# Connectors.net
KiCad netlist of a schematic drawn in Altium Designer
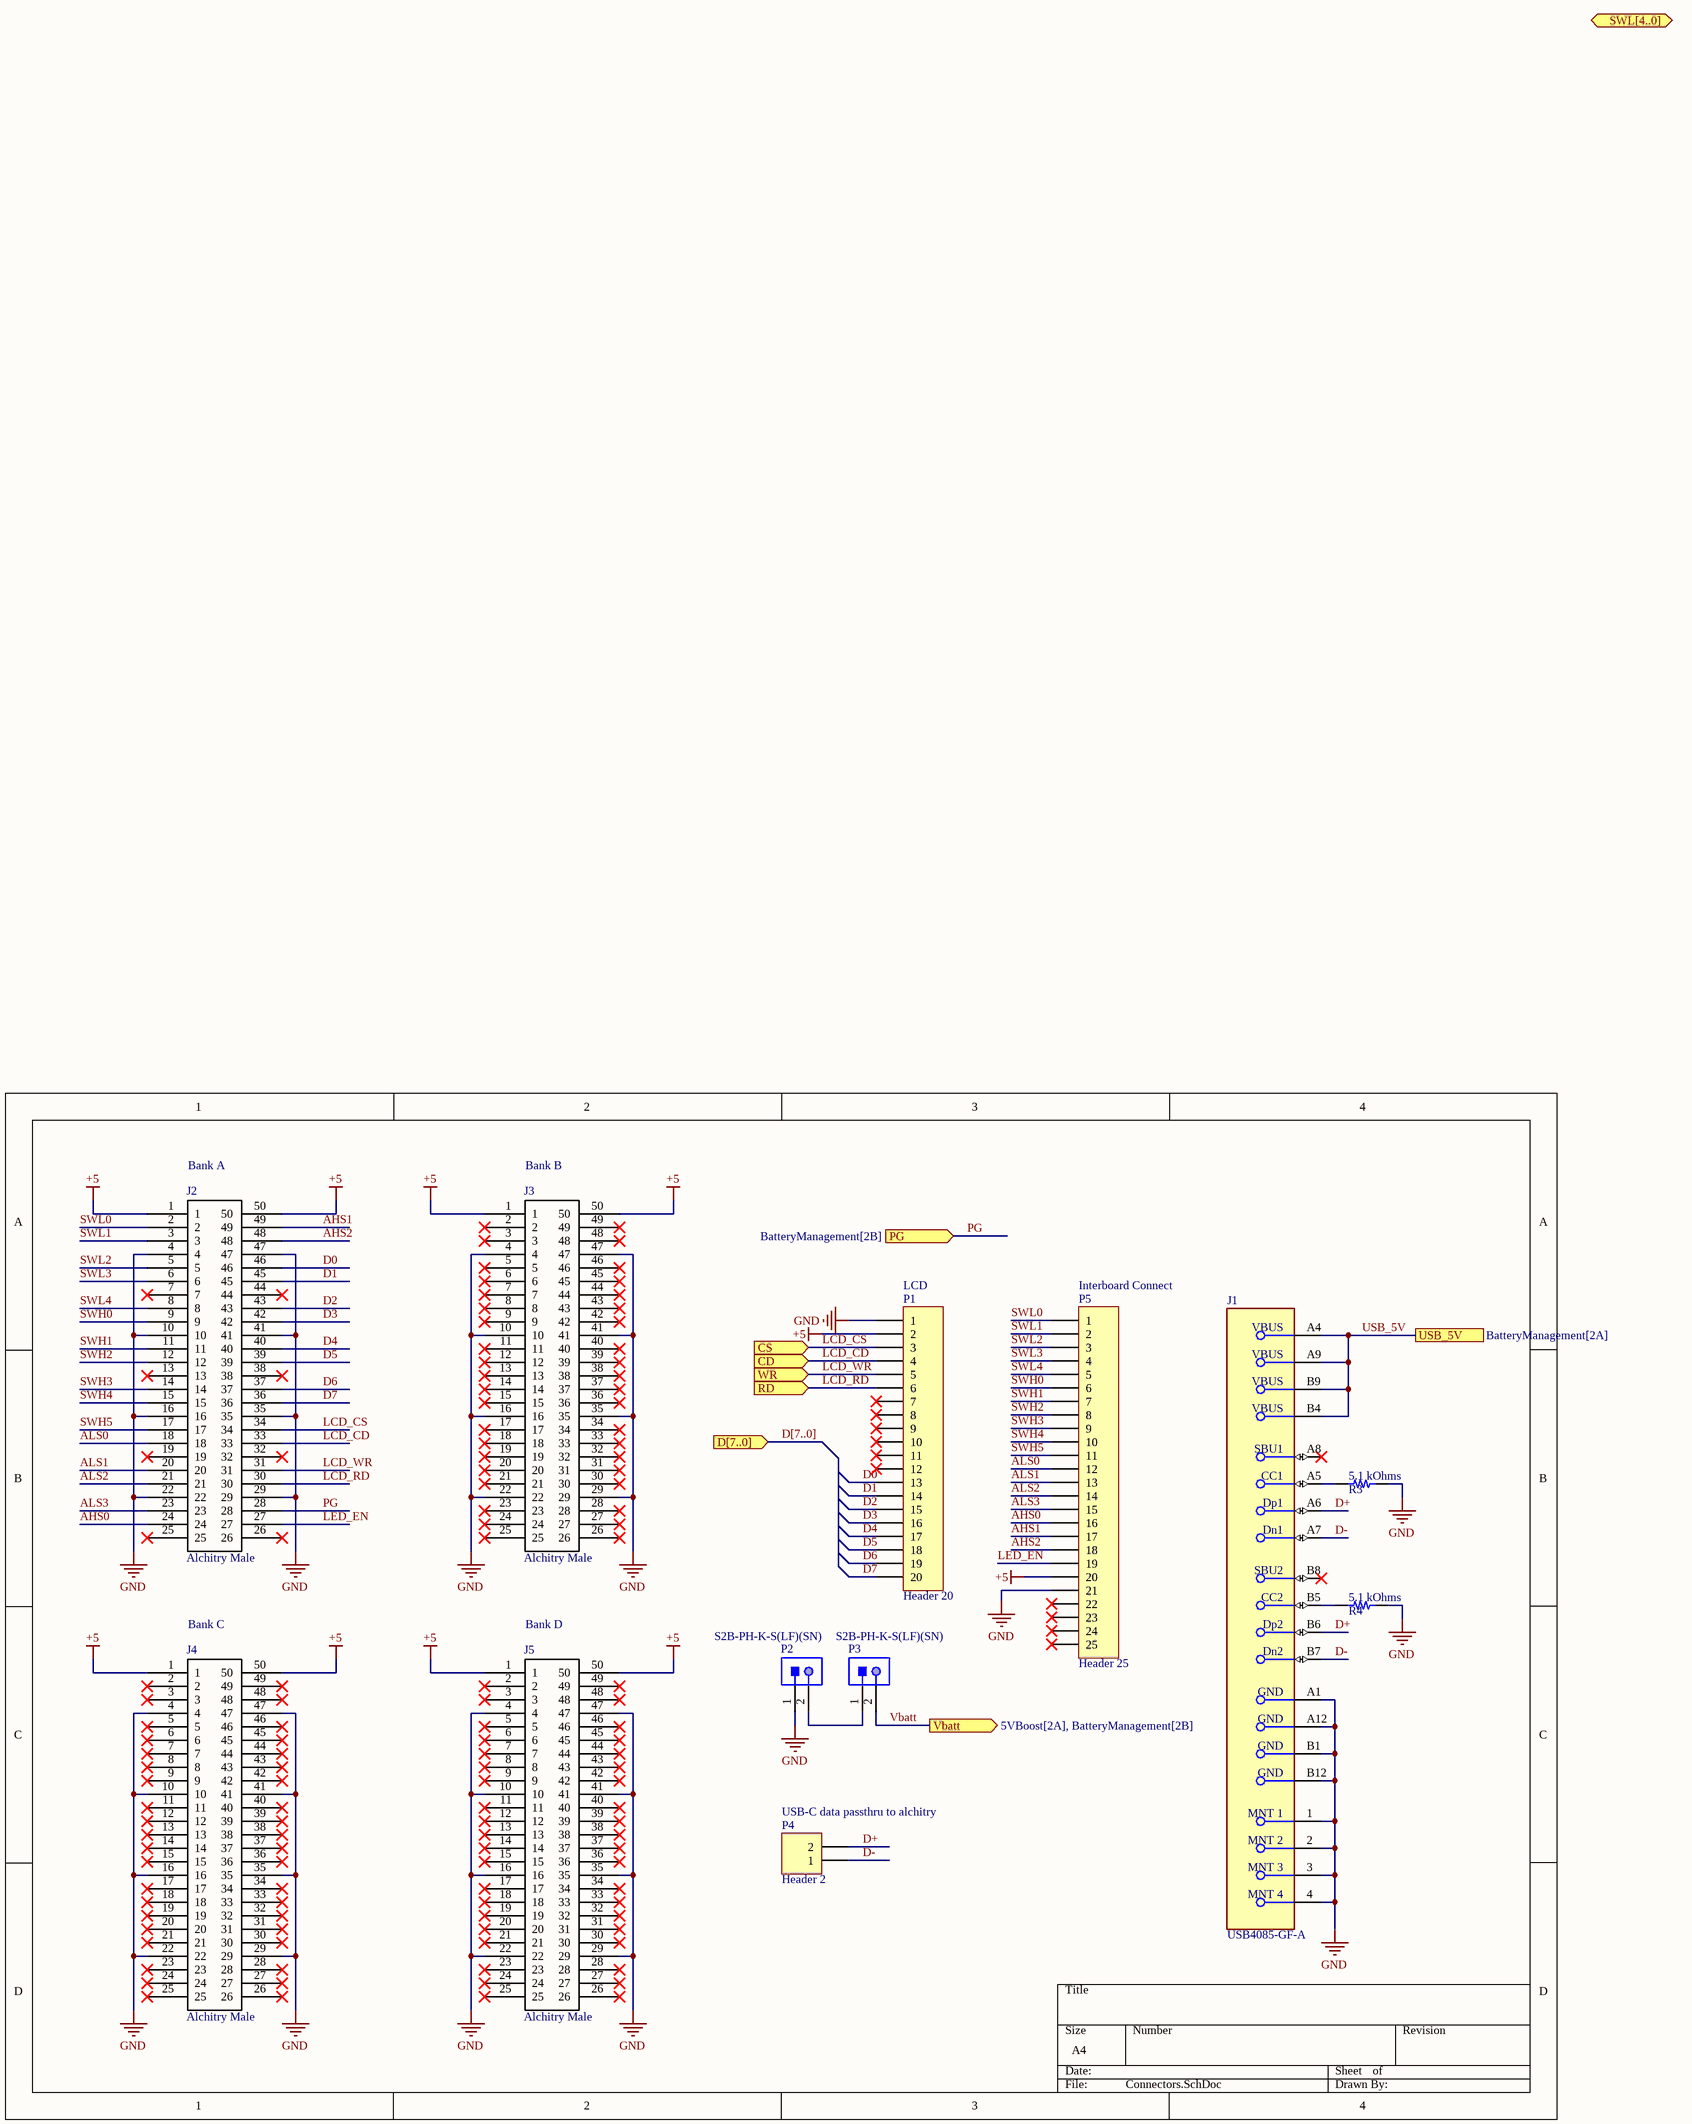
[diagram p0: Connectors.SchDoc]

(export (version "E")
  (design (tool "Eeschema 10.0.6"))
  (components
    (comp (ref "J1")
      (value "USB4085-GF-A")
      (footprint "FP-USB4085-GF-A-MFG")
      (description "CONN RCPT USB2.0 TYPE C 24POS RA")
      (libsource (lib "Altium Content Vault") (part "10fa745527c8b974685cbca3c197132"))
    )
    (comp (ref "J2")
      (value "Alchitry Male")
      (footprint "AlchitryMale")
      (libsource (lib "2020-09-26_17-27-19") (part "Alchitry Male"))
    )
    (comp (ref "J3")
      (value "Alchitry Male")
      (footprint "AlchitryMale")
      (libsource (lib "2020-09-26_17-27-19") (part "Alchitry Male"))
    )
    (comp (ref "J4")
      (value "Alchitry Male")
      (footprint "AlchitryMale")
      (libsource (lib "2020-09-26_17-27-19") (part "Alchitry Male"))
    )
    (comp (ref "J5")
      (value "Alchitry Male")
      (footprint "AlchitryMale")
      (libsource (lib "2020-09-26_17-27-19") (part "Alchitry Male"))
    )
    (comp (ref "P1")
      (value "Header 20")
      (footprint "HDR1X20")
      (description "Header, 20-Pin")
      (fields (field (name "PUBLISHER") "Altium Limited"))
      (libsource (lib "Miscellaneous Connectors") (part "Header 20"))
    )
    (comp (ref "P2")
      (value "S2B-PH-K-S(LF)(SN)")
      (footprint "JST-S2B-PH-K-S_V")
      (fields (field (name "TOLERANCE") "20%"))
      (libsource (lib "Altium Content Vault") (part "CN-1P-M-R2"))
    )
    (comp (ref "P3")
      (value "S2B-PH-K-S(LF)(SN)")
      (footprint "JST-S2B-PH-K-S_V")
      (fields (field (name "TOLERANCE") "20%"))
      (libsource (lib "Altium Content Vault") (part "CN-1P-M-R2"))
    )
    (comp (ref "P4")
      (value "Header 2")
      (footprint "HDR1X2")
      (description "Header, 2-Pin")
      (fields (field (name "PUBLISHER") "Altium Limited"))
      (libsource (lib "Miscellaneous Connectors") (part "Header 2"))
    )
    (comp (ref "P5")
      (value "Header 25")
      (footprint "HDR1X25")
      (description "Header, 25-Pin")
      (fields (field (name "PUBLISHER") "Altium Limited"))
      (libsource (lib "Miscellaneous Connectors") (part "Header 25"))
    )
    (comp (ref "R3")
      (value "5.1 kOhms")
      (footprint "RES 0805_2012")
      (description "RES 5.1K OHM 5% 1/8W 0805")
      (fields (field (name "PART NUMBER") "RC0805JR-075K1L") (field (name "MANUFACTURER") "Yageo"))
      (libsource (lib "Celestial Altium Library - altium_library") (part "Resistor"))
    )
    (comp (ref "R4")
      (value "5.1 kOhms")
      (footprint "RES 0805_2012")
      (description "RES 5.1K OHM 5% 1/8W 0805")
      (fields (field (name "PART NUMBER") "RC0805JR-075K1L") (field (name "MANUFACTURER") "Yageo"))
      (libsource (lib "Celestial Altium Library - altium_library") (part "Resistor"))
    )
  )
  (nets
    (net (code "1") (name "+5") (class "Default")
      (node (ref "J2") (pin "1") (pinfunction "1_1") (pintype "passive"))
      (node (ref "J2") (pin "50") (pinfunction "50_50") (pintype "passive"))
      (node (ref "J3") (pin "1") (pinfunction "1_1") (pintype "passive"))
      (node (ref "J3") (pin "50") (pinfunction "50_50") (pintype "passive"))
      (node (ref "J4") (pin "1") (pinfunction "1_1") (pintype "passive"))
      (node (ref "J4") (pin "50") (pinfunction "50_50") (pintype "passive"))
      (node (ref "J5") (pin "1") (pinfunction "1_1") (pintype "passive"))
      (node (ref "J5") (pin "50") (pinfunction "50_50") (pintype "passive"))
      (node (ref "P1") (pin "2") (pinfunction "2_2") (pintype "passive"))
      (node (ref "P5") (pin "20") (pinfunction "20_20") (pintype "passive"))
    )
    (net (code "2") (name "/AHS0") (class "Default")
      (node (ref "J2") (pin "24") (pinfunction "24_24") (pintype "passive"))
      (node (ref "P5") (pin "16") (pinfunction "16_16") (pintype "passive"))
    )
    (net (code "3") (name "/AHS1") (class "Default")
      (node (ref "J2") (pin "49") (pinfunction "49_49") (pintype "passive"))
      (node (ref "P5") (pin "17") (pinfunction "17_17") (pintype "passive"))
    )
    (net (code "4") (name "/AHS2") (class "Default")
      (node (ref "J2") (pin "48") (pinfunction "48_48") (pintype "passive"))
      (node (ref "P5") (pin "18") (pinfunction "18_18") (pintype "passive"))
    )
    (net (code "5") (name "/ALS0") (class "Default")
      (node (ref "J2") (pin "18") (pinfunction "18_18") (pintype "passive"))
      (node (ref "P5") (pin "12") (pinfunction "12_12") (pintype "passive"))
    )
    (net (code "6") (name "/ALS1") (class "Default")
      (node (ref "J2") (pin "20") (pinfunction "20_20") (pintype "passive"))
      (node (ref "P5") (pin "13") (pinfunction "13_13") (pintype "passive"))
    )
    (net (code "7") (name "/ALS2") (class "Default")
      (node (ref "J2") (pin "21") (pinfunction "21_21") (pintype "passive"))
      (node (ref "P5") (pin "14") (pinfunction "14_14") (pintype "passive"))
    )
    (net (code "8") (name "/ALS3") (class "Default")
      (node (ref "J2") (pin "23") (pinfunction "23_23") (pintype "passive"))
      (node (ref "P5") (pin "15") (pinfunction "15_15") (pintype "passive"))
    )
    (net (code "9") (name "/D+") (class "Default")
      (node (ref "J1") (pin "A6") (pinfunction "Dp1_A6") (pintype "bidirectional"))
      (node (ref "J1") (pin "B6") (pinfunction "Dp2_B6") (pintype "bidirectional"))
      (node (ref "P4") (pin "2") (pinfunction "2_2") (pintype "passive"))
    )
    (net (code "10") (name "/D-") (class "Default")
      (node (ref "J1") (pin "A7") (pinfunction "Dn1_A7") (pintype "bidirectional"))
      (node (ref "J1") (pin "B7") (pinfunction "Dn2_B7") (pintype "bidirectional"))
      (node (ref "P4") (pin "1") (pinfunction "1_1") (pintype "passive"))
    )
    (net (code "11") (name "/D0") (class "Default")
      (node (ref "J2") (pin "46") (pinfunction "46_46") (pintype "passive"))
      (node (ref "P1") (pin "13") (pinfunction "13_13") (pintype "passive"))
    )
    (net (code "12") (name "/D1") (class "Default")
      (node (ref "J2") (pin "45") (pinfunction "45_45") (pintype "passive"))
      (node (ref "P1") (pin "14") (pinfunction "14_14") (pintype "passive"))
    )
    (net (code "13") (name "/D2") (class "Default")
      (node (ref "J2") (pin "43") (pinfunction "43_43") (pintype "passive"))
      (node (ref "P1") (pin "15") (pinfunction "15_15") (pintype "passive"))
    )
    (net (code "14") (name "/D3") (class "Default")
      (node (ref "J2") (pin "42") (pinfunction "42_42") (pintype "passive"))
      (node (ref "P1") (pin "16") (pinfunction "16_16") (pintype "passive"))
    )
    (net (code "15") (name "/D4") (class "Default")
      (node (ref "J2") (pin "40") (pinfunction "40_40") (pintype "passive"))
      (node (ref "P1") (pin "17") (pinfunction "17_17") (pintype "passive"))
    )
    (net (code "16") (name "/D5") (class "Default")
      (node (ref "J2") (pin "39") (pinfunction "39_39") (pintype "passive"))
      (node (ref "P1") (pin "18") (pinfunction "18_18") (pintype "passive"))
    )
    (net (code "17") (name "/D6") (class "Default")
      (node (ref "J2") (pin "37") (pinfunction "37_37") (pintype "passive"))
      (node (ref "P1") (pin "19") (pinfunction "19_19") (pintype "passive"))
    )
    (net (code "18") (name "/D7") (class "Default")
      (node (ref "J2") (pin "36") (pinfunction "36_36") (pintype "passive"))
      (node (ref "P1") (pin "20") (pinfunction "20_20") (pintype "passive"))
    )
    (net (code "20") (name "/LCD_CD") (class "Default")
      (node (ref "J2") (pin "33") (pinfunction "33_33") (pintype "passive"))
      (node (ref "P1") (pin "4") (pinfunction "4_4") (pintype "passive"))
    )
    (net (code "21") (name "/LCD_CS") (class "Default")
      (node (ref "J2") (pin "34") (pinfunction "34_34") (pintype "passive"))
      (node (ref "P1") (pin "3") (pinfunction "3_3") (pintype "passive"))
    )
    (net (code "22") (name "/LCD_RD") (class "Default")
      (node (ref "J2") (pin "30") (pinfunction "30_30") (pintype "passive"))
      (node (ref "P1") (pin "6") (pinfunction "6_6") (pintype "passive"))
    )
    (net (code "23") (name "/LCD_WR") (class "Default")
      (node (ref "J2") (pin "31") (pinfunction "31_31") (pintype "passive"))
      (node (ref "P1") (pin "5") (pinfunction "5_5") (pintype "passive"))
    )
    (net (code "24") (name "/LED_EN") (class "Default")
      (node (ref "J2") (pin "27") (pinfunction "27_27") (pintype "passive"))
      (node (ref "P5") (pin "19") (pinfunction "19_19") (pintype "passive"))
    )
    (net (code "25") (name "/PG") (class "Default")
      (node (ref "J2") (pin "28") (pinfunction "28_28") (pintype "passive"))
    )
    (net (code "26") (name "/SWH0") (class "Default")
      (node (ref "J2") (pin "9") (pinfunction "9_9") (pintype "passive"))
      (node (ref "P5") (pin "6") (pinfunction "6_6") (pintype "passive"))
    )
    (net (code "27") (name "/SWH1") (class "Default")
      (node (ref "J2") (pin "11") (pinfunction "11_11") (pintype "passive"))
      (node (ref "P5") (pin "7") (pinfunction "7_7") (pintype "passive"))
    )
    (net (code "28") (name "/SWH2") (class "Default")
      (node (ref "J2") (pin "12") (pinfunction "12_12") (pintype "passive"))
      (node (ref "P5") (pin "8") (pinfunction "8_8") (pintype "passive"))
    )
    (net (code "29") (name "/SWH3") (class "Default")
      (node (ref "J2") (pin "14") (pinfunction "14_14") (pintype "passive"))
      (node (ref "P5") (pin "9") (pinfunction "9_9") (pintype "passive"))
    )
    (net (code "30") (name "/SWH4") (class "Default")
      (node (ref "J2") (pin "15") (pinfunction "15_15") (pintype "passive"))
      (node (ref "P5") (pin "10") (pinfunction "10_10") (pintype "passive"))
    )
    (net (code "31") (name "/SWH5") (class "Default")
      (node (ref "J2") (pin "17") (pinfunction "17_17") (pintype "passive"))
      (node (ref "P5") (pin "11") (pinfunction "11_11") (pintype "passive"))
    )
    (net (code "32") (name "/SWL0") (class "Default")
      (node (ref "J2") (pin "2") (pinfunction "2_2") (pintype "passive"))
      (node (ref "P5") (pin "1") (pinfunction "1_1") (pintype "passive"))
    )
    (net (code "33") (name "/SWL1") (class "Default")
      (node (ref "J2") (pin "3") (pinfunction "3_3") (pintype "passive"))
      (node (ref "P5") (pin "2") (pinfunction "2_2") (pintype "passive"))
    )
    (net (code "34") (name "/SWL2") (class "Default")
      (node (ref "J2") (pin "5") (pinfunction "5_5") (pintype "passive"))
      (node (ref "P5") (pin "3") (pinfunction "3_3") (pintype "passive"))
    )
    (net (code "35") (name "/SWL3") (class "Default")
      (node (ref "J2") (pin "6") (pinfunction "6_6") (pintype "passive"))
      (node (ref "P5") (pin "4") (pinfunction "4_4") (pintype "passive"))
    )
    (net (code "36") (name "/SWL4") (class "Default")
      (node (ref "J2") (pin "8") (pinfunction "8_8") (pintype "passive"))
      (node (ref "P5") (pin "5") (pinfunction "5_5") (pintype "passive"))
    )
    (net (code "38") (name "/USB_5V") (class "Default")
      (node (ref "J1") (pin "A4") (pinfunction "VBUS_A4") (pintype "power_in"))
      (node (ref "J1") (pin "A9") (pinfunction "VBUS_A9") (pintype "power_in"))
      (node (ref "J1") (pin "B4") (pinfunction "VBUS_B4") (pintype "power_in"))
      (node (ref "J1") (pin "B9") (pinfunction "VBUS_B9") (pintype "power_in"))
    )
    (net (code "39") (name "/Vbatt") (class "Default")
      (node (ref "P3") (pin "2") (pinfunction "2_2") (pintype "passive"))
    )
    (net (code "40") (name "GND") (class "Default")
      (node (ref "J1") (pin "1") (pinfunction "MNT_1_1") (pintype "passive"))
      (node (ref "J1") (pin "2") (pinfunction "MNT_2_2") (pintype "passive"))
      (node (ref "J1") (pin "3") (pinfunction "MNT_3_3") (pintype "passive"))
      (node (ref "J1") (pin "4") (pinfunction "MNT_4_4") (pintype "passive"))
      (node (ref "J1") (pin "A1") (pinfunction "GND_A1") (pintype "power_in"))
      (node (ref "J1") (pin "A12") (pinfunction "GND_A12") (pintype "power_in"))
      (node (ref "J1") (pin "B1") (pinfunction "GND_B1") (pintype "power_in"))
      (node (ref "J1") (pin "B12") (pinfunction "GND_B12") (pintype "power_in"))
      (node (ref "J2") (pin "10") (pinfunction "10_10") (pintype "passive"))
      (node (ref "J2") (pin "16") (pinfunction "16_16") (pintype "passive"))
      (node (ref "J2") (pin "22") (pinfunction "22_22") (pintype "passive"))
      (node (ref "J2") (pin "29") (pinfunction "29_29") (pintype "passive"))
      (node (ref "J2") (pin "35") (pinfunction "35_35") (pintype "passive"))
      (node (ref "J2") (pin "4") (pinfunction "4_4") (pintype "passive"))
      (node (ref "J2") (pin "41") (pinfunction "41_41") (pintype "passive"))
      (node (ref "J2") (pin "47") (pinfunction "47_47") (pintype "passive"))
      (node (ref "J3") (pin "10") (pinfunction "10_10") (pintype "passive"))
      (node (ref "J3") (pin "16") (pinfunction "16_16") (pintype "passive"))
      (node (ref "J3") (pin "22") (pinfunction "22_22") (pintype "passive"))
      (node (ref "J3") (pin "29") (pinfunction "29_29") (pintype "passive"))
      (node (ref "J3") (pin "35") (pinfunction "35_35") (pintype "passive"))
      (node (ref "J3") (pin "4") (pinfunction "4_4") (pintype "passive"))
      (node (ref "J3") (pin "41") (pinfunction "41_41") (pintype "passive"))
      (node (ref "J3") (pin "47") (pinfunction "47_47") (pintype "passive"))
      (node (ref "J4") (pin "10") (pinfunction "10_10") (pintype "passive"))
      (node (ref "J4") (pin "16") (pinfunction "16_16") (pintype "passive"))
      (node (ref "J4") (pin "22") (pinfunction "22_22") (pintype "passive"))
      (node (ref "J4") (pin "29") (pinfunction "29_29") (pintype "passive"))
      (node (ref "J4") (pin "35") (pinfunction "35_35") (pintype "passive"))
      (node (ref "J4") (pin "4") (pinfunction "4_4") (pintype "passive"))
      (node (ref "J4") (pin "41") (pinfunction "41_41") (pintype "passive"))
      (node (ref "J4") (pin "47") (pinfunction "47_47") (pintype "passive"))
      (node (ref "J5") (pin "10") (pinfunction "10_10") (pintype "passive"))
      (node (ref "J5") (pin "16") (pinfunction "16_16") (pintype "passive"))
      (node (ref "J5") (pin "22") (pinfunction "22_22") (pintype "passive"))
      (node (ref "J5") (pin "29") (pinfunction "29_29") (pintype "passive"))
      (node (ref "J5") (pin "35") (pinfunction "35_35") (pintype "passive"))
      (node (ref "J5") (pin "4") (pinfunction "4_4") (pintype "passive"))
      (node (ref "J5") (pin "41") (pinfunction "41_41") (pintype "passive"))
      (node (ref "J5") (pin "47") (pinfunction "47_47") (pintype "passive"))
      (node (ref "P1") (pin "1") (pinfunction "1_1") (pintype "passive"))
      (node (ref "P2") (pin "1") (pinfunction "1_1") (pintype "passive"))
      (node (ref "P5") (pin "21") (pinfunction "21_21") (pintype "passive"))
      (node (ref "R3") (pin "2") (pinfunction "2_2") (pintype "passive"))
      (node (ref "R4") (pin "2") (pinfunction "2_2") (pintype "passive"))
    )
    (net (code "41") (name "Net-(J1-CC1)") (class "Default")
      (node (ref "J1") (pin "A5") (pinfunction "CC1_A5") (pintype "bidirectional"))
      (node (ref "R3") (pin "1") (pinfunction "1_1") (pintype "passive"))
    )
    (net (code "42") (name "Net-(J1-CC2)") (class "Default")
      (node (ref "J1") (pin "B5") (pinfunction "CC2_B5") (pintype "bidirectional"))
      (node (ref "R4") (pin "1") (pinfunction "1_1") (pintype "passive"))
    )
    (net (code "43") (name "Net-(P2-Pad2)") (class "Default")
      (node (ref "P2") (pin "2") (pinfunction "2_2") (pintype "passive"))
      (node (ref "P3") (pin "1") (pinfunction "1_1") (pintype "passive"))
    )
    (net (code "44") (name "unconnected-(J1-SBU1-PadA8)") (class "Default")
      (node (ref "J1") (pin "A8") (pinfunction "SBU1_A8") (pintype "bidirectional+no_connect"))
    )
    (net (code "45") (name "unconnected-(J1-SBU2-PadB8)") (class "Default")
      (node (ref "J1") (pin "B8") (pinfunction "SBU2_B8") (pintype "bidirectional+no_connect"))
    )
    (net (code "46") (name "unconnected-(J2-Pad7)") (class "Default")
      (node (ref "J2") (pin "7") (pinfunction "7_7") (pintype "passive+no_connect"))
    )
    (net (code "47") (name "unconnected-(J2-Pad13)") (class "Default")
      (node (ref "J2") (pin "13") (pinfunction "13_13") (pintype "passive+no_connect"))
    )
    (net (code "48") (name "unconnected-(J2-Pad19)") (class "Default")
      (node (ref "J2") (pin "19") (pinfunction "19_19") (pintype "passive+no_connect"))
    )
    (net (code "49") (name "unconnected-(J2-Pad25)") (class "Default")
      (node (ref "J2") (pin "25") (pinfunction "25_25") (pintype "passive+no_connect"))
    )
    (net (code "50") (name "unconnected-(J2-Pad26)") (class "Default")
      (node (ref "J2") (pin "26") (pinfunction "26_26") (pintype "passive+no_connect"))
    )
    (net (code "51") (name "unconnected-(J2-Pad32)") (class "Default")
      (node (ref "J2") (pin "32") (pinfunction "32_32") (pintype "passive+no_connect"))
    )
    (net (code "52") (name "unconnected-(J2-Pad38)") (class "Default")
      (node (ref "J2") (pin "38") (pinfunction "38_38") (pintype "passive+no_connect"))
    )
    (net (code "53") (name "unconnected-(J2-Pad44)") (class "Default")
      (node (ref "J2") (pin "44") (pinfunction "44_44") (pintype "passive+no_connect"))
    )
    (net (code "54") (name "unconnected-(J3-Pad2)") (class "Default")
      (node (ref "J3") (pin "2") (pinfunction "2_2") (pintype "passive+no_connect"))
    )
    (net (code "55") (name "unconnected-(J3-Pad3)") (class "Default")
      (node (ref "J3") (pin "3") (pinfunction "3_3") (pintype "passive+no_connect"))
    )
    (net (code "56") (name "unconnected-(J3-Pad5)") (class "Default")
      (node (ref "J3") (pin "5") (pinfunction "5_5") (pintype "passive+no_connect"))
    )
    (net (code "57") (name "unconnected-(J3-Pad6)") (class "Default")
      (node (ref "J3") (pin "6") (pinfunction "6_6") (pintype "passive+no_connect"))
    )
    (net (code "58") (name "unconnected-(J3-Pad7)") (class "Default")
      (node (ref "J3") (pin "7") (pinfunction "7_7") (pintype "passive+no_connect"))
    )
    (net (code "59") (name "unconnected-(J3-Pad8)") (class "Default")
      (node (ref "J3") (pin "8") (pinfunction "8_8") (pintype "passive+no_connect"))
    )
    (net (code "60") (name "unconnected-(J3-Pad9)") (class "Default")
      (node (ref "J3") (pin "9") (pinfunction "9_9") (pintype "passive+no_connect"))
    )
    (net (code "61") (name "unconnected-(J3-Pad11)") (class "Default")
      (node (ref "J3") (pin "11") (pinfunction "11_11") (pintype "passive+no_connect"))
    )
    (net (code "62") (name "unconnected-(J3-Pad12)") (class "Default")
      (node (ref "J3") (pin "12") (pinfunction "12_12") (pintype "passive+no_connect"))
    )
    (net (code "63") (name "unconnected-(J3-Pad13)") (class "Default")
      (node (ref "J3") (pin "13") (pinfunction "13_13") (pintype "passive+no_connect"))
    )
    (net (code "64") (name "unconnected-(J3-Pad14)") (class "Default")
      (node (ref "J3") (pin "14") (pinfunction "14_14") (pintype "passive+no_connect"))
    )
    (net (code "65") (name "unconnected-(J3-Pad15)") (class "Default")
      (node (ref "J3") (pin "15") (pinfunction "15_15") (pintype "passive+no_connect"))
    )
    (net (code "66") (name "unconnected-(J3-Pad17)") (class "Default")
      (node (ref "J3") (pin "17") (pinfunction "17_17") (pintype "passive+no_connect"))
    )
    (net (code "67") (name "unconnected-(J3-Pad18)") (class "Default")
      (node (ref "J3") (pin "18") (pinfunction "18_18") (pintype "passive+no_connect"))
    )
    (net (code "68") (name "unconnected-(J3-Pad19)") (class "Default")
      (node (ref "J3") (pin "19") (pinfunction "19_19") (pintype "passive+no_connect"))
    )
    (net (code "69") (name "unconnected-(J3-Pad20)") (class "Default")
      (node (ref "J3") (pin "20") (pinfunction "20_20") (pintype "passive+no_connect"))
    )
    (net (code "70") (name "unconnected-(J3-Pad21)") (class "Default")
      (node (ref "J3") (pin "21") (pinfunction "21_21") (pintype "passive+no_connect"))
    )
    (net (code "71") (name "unconnected-(J3-Pad23)") (class "Default")
      (node (ref "J3") (pin "23") (pinfunction "23_23") (pintype "passive+no_connect"))
    )
    (net (code "72") (name "unconnected-(J3-Pad24)") (class "Default")
      (node (ref "J3") (pin "24") (pinfunction "24_24") (pintype "passive+no_connect"))
    )
    (net (code "73") (name "unconnected-(J3-Pad25)") (class "Default")
      (node (ref "J3") (pin "25") (pinfunction "25_25") (pintype "passive+no_connect"))
    )
    (net (code "74") (name "unconnected-(J3-Pad26)") (class "Default")
      (node (ref "J3") (pin "26") (pinfunction "26_26") (pintype "passive+no_connect"))
    )
    (net (code "75") (name "unconnected-(J3-Pad27)") (class "Default")
      (node (ref "J3") (pin "27") (pinfunction "27_27") (pintype "passive+no_connect"))
    )
    (net (code "76") (name "unconnected-(J3-Pad28)") (class "Default")
      (node (ref "J3") (pin "28") (pinfunction "28_28") (pintype "passive+no_connect"))
    )
    (net (code "77") (name "unconnected-(J3-Pad30)") (class "Default")
      (node (ref "J3") (pin "30") (pinfunction "30_30") (pintype "passive+no_connect"))
    )
    (net (code "78") (name "unconnected-(J3-Pad31)") (class "Default")
      (node (ref "J3") (pin "31") (pinfunction "31_31") (pintype "passive+no_connect"))
    )
    (net (code "79") (name "unconnected-(J3-Pad32)") (class "Default")
      (node (ref "J3") (pin "32") (pinfunction "32_32") (pintype "passive+no_connect"))
    )
    (net (code "80") (name "unconnected-(J3-Pad33)") (class "Default")
      (node (ref "J3") (pin "33") (pinfunction "33_33") (pintype "passive+no_connect"))
    )
    (net (code "81") (name "unconnected-(J3-Pad34)") (class "Default")
      (node (ref "J3") (pin "34") (pinfunction "34_34") (pintype "passive+no_connect"))
    )
    (net (code "82") (name "unconnected-(J3-Pad36)") (class "Default")
      (node (ref "J3") (pin "36") (pinfunction "36_36") (pintype "passive+no_connect"))
    )
    (net (code "83") (name "unconnected-(J3-Pad37)") (class "Default")
      (node (ref "J3") (pin "37") (pinfunction "37_37") (pintype "passive+no_connect"))
    )
    (net (code "84") (name "unconnected-(J3-Pad38)") (class "Default")
      (node (ref "J3") (pin "38") (pinfunction "38_38") (pintype "passive+no_connect"))
    )
    (net (code "85") (name "unconnected-(J3-Pad39)") (class "Default")
      (node (ref "J3") (pin "39") (pinfunction "39_39") (pintype "passive+no_connect"))
    )
    (net (code "86") (name "unconnected-(J3-Pad40)") (class "Default")
      (node (ref "J3") (pin "40") (pinfunction "40_40") (pintype "passive+no_connect"))
    )
    (net (code "87") (name "unconnected-(J3-Pad42)") (class "Default")
      (node (ref "J3") (pin "42") (pinfunction "42_42") (pintype "passive+no_connect"))
    )
    (net (code "88") (name "unconnected-(J3-Pad43)") (class "Default")
      (node (ref "J3") (pin "43") (pinfunction "43_43") (pintype "passive+no_connect"))
    )
    (net (code "89") (name "unconnected-(J3-Pad44)") (class "Default")
      (node (ref "J3") (pin "44") (pinfunction "44_44") (pintype "passive+no_connect"))
    )
    (net (code "90") (name "unconnected-(J3-Pad45)") (class "Default")
      (node (ref "J3") (pin "45") (pinfunction "45_45") (pintype "passive+no_connect"))
    )
    (net (code "91") (name "unconnected-(J3-Pad46)") (class "Default")
      (node (ref "J3") (pin "46") (pinfunction "46_46") (pintype "passive+no_connect"))
    )
    (net (code "92") (name "unconnected-(J3-Pad48)") (class "Default")
      (node (ref "J3") (pin "48") (pinfunction "48_48") (pintype "passive+no_connect"))
    )
    (net (code "93") (name "unconnected-(J3-Pad49)") (class "Default")
      (node (ref "J3") (pin "49") (pinfunction "49_49") (pintype "passive+no_connect"))
    )
    (net (code "94") (name "unconnected-(J4-Pad2)") (class "Default")
      (node (ref "J4") (pin "2") (pinfunction "2_2") (pintype "passive+no_connect"))
    )
    (net (code "95") (name "unconnected-(J4-Pad3)") (class "Default")
      (node (ref "J4") (pin "3") (pinfunction "3_3") (pintype "passive+no_connect"))
    )
    (net (code "96") (name "unconnected-(J4-Pad5)") (class "Default")
      (node (ref "J4") (pin "5") (pinfunction "5_5") (pintype "passive+no_connect"))
    )
    (net (code "97") (name "unconnected-(J4-Pad6)") (class "Default")
      (node (ref "J4") (pin "6") (pinfunction "6_6") (pintype "passive+no_connect"))
    )
    (net (code "98") (name "unconnected-(J4-Pad7)") (class "Default")
      (node (ref "J4") (pin "7") (pinfunction "7_7") (pintype "passive+no_connect"))
    )
    (net (code "99") (name "unconnected-(J4-Pad8)") (class "Default")
      (node (ref "J4") (pin "8") (pinfunction "8_8") (pintype "passive+no_connect"))
    )
    (net (code "100") (name "unconnected-(J4-Pad9)") (class "Default")
      (node (ref "J4") (pin "9") (pinfunction "9_9") (pintype "passive+no_connect"))
    )
    (net (code "101") (name "unconnected-(J4-Pad11)") (class "Default")
      (node (ref "J4") (pin "11") (pinfunction "11_11") (pintype "passive+no_connect"))
    )
    (net (code "102") (name "unconnected-(J4-Pad12)") (class "Default")
      (node (ref "J4") (pin "12") (pinfunction "12_12") (pintype "passive+no_connect"))
    )
    (net (code "103") (name "unconnected-(J4-Pad13)") (class "Default")
      (node (ref "J4") (pin "13") (pinfunction "13_13") (pintype "passive+no_connect"))
    )
    (net (code "104") (name "unconnected-(J4-Pad14)") (class "Default")
      (node (ref "J4") (pin "14") (pinfunction "14_14") (pintype "passive+no_connect"))
    )
    (net (code "105") (name "unconnected-(J4-Pad15)") (class "Default")
      (node (ref "J4") (pin "15") (pinfunction "15_15") (pintype "passive+no_connect"))
    )
    (net (code "106") (name "unconnected-(J4-Pad17)") (class "Default")
      (node (ref "J4") (pin "17") (pinfunction "17_17") (pintype "passive+no_connect"))
    )
    (net (code "107") (name "unconnected-(J4-Pad18)") (class "Default")
      (node (ref "J4") (pin "18") (pinfunction "18_18") (pintype "passive+no_connect"))
    )
    (net (code "108") (name "unconnected-(J4-Pad19)") (class "Default")
      (node (ref "J4") (pin "19") (pinfunction "19_19") (pintype "passive+no_connect"))
    )
    (net (code "109") (name "unconnected-(J4-Pad20)") (class "Default")
      (node (ref "J4") (pin "20") (pinfunction "20_20") (pintype "passive+no_connect"))
    )
    (net (code "110") (name "unconnected-(J4-Pad21)") (class "Default")
      (node (ref "J4") (pin "21") (pinfunction "21_21") (pintype "passive+no_connect"))
    )
    (net (code "111") (name "unconnected-(J4-Pad23)") (class "Default")
      (node (ref "J4") (pin "23") (pinfunction "23_23") (pintype "passive+no_connect"))
    )
    (net (code "112") (name "unconnected-(J4-Pad24)") (class "Default")
      (node (ref "J4") (pin "24") (pinfunction "24_24") (pintype "passive+no_connect"))
    )
    (net (code "113") (name "unconnected-(J4-Pad25)") (class "Default")
      (node (ref "J4") (pin "25") (pinfunction "25_25") (pintype "passive+no_connect"))
    )
    (net (code "114") (name "unconnected-(J4-Pad26)") (class "Default")
      (node (ref "J4") (pin "26") (pinfunction "26_26") (pintype "passive+no_connect"))
    )
    (net (code "115") (name "unconnected-(J4-Pad27)") (class "Default")
      (node (ref "J4") (pin "27") (pinfunction "27_27") (pintype "passive+no_connect"))
    )
    (net (code "116") (name "unconnected-(J4-Pad28)") (class "Default")
      (node (ref "J4") (pin "28") (pinfunction "28_28") (pintype "passive+no_connect"))
    )
    (net (code "117") (name "unconnected-(J4-Pad30)") (class "Default")
      (node (ref "J4") (pin "30") (pinfunction "30_30") (pintype "passive+no_connect"))
    )
    (net (code "118") (name "unconnected-(J4-Pad31)") (class "Default")
      (node (ref "J4") (pin "31") (pinfunction "31_31") (pintype "passive+no_connect"))
    )
    (net (code "119") (name "unconnected-(J4-Pad32)") (class "Default")
      (node (ref "J4") (pin "32") (pinfunction "32_32") (pintype "passive+no_connect"))
    )
    (net (code "120") (name "unconnected-(J4-Pad33)") (class "Default")
      (node (ref "J4") (pin "33") (pinfunction "33_33") (pintype "passive+no_connect"))
    )
    (net (code "121") (name "unconnected-(J4-Pad34)") (class "Default")
      (node (ref "J4") (pin "34") (pinfunction "34_34") (pintype "passive+no_connect"))
    )
    (net (code "122") (name "unconnected-(J4-Pad36)") (class "Default")
      (node (ref "J4") (pin "36") (pinfunction "36_36") (pintype "passive+no_connect"))
    )
    (net (code "123") (name "unconnected-(J4-Pad37)") (class "Default")
      (node (ref "J4") (pin "37") (pinfunction "37_37") (pintype "passive+no_connect"))
    )
    (net (code "124") (name "unconnected-(J4-Pad38)") (class "Default")
      (node (ref "J4") (pin "38") (pinfunction "38_38") (pintype "passive+no_connect"))
    )
    (net (code "125") (name "unconnected-(J4-Pad39)") (class "Default")
      (node (ref "J4") (pin "39") (pinfunction "39_39") (pintype "passive+no_connect"))
    )
    (net (code "126") (name "unconnected-(J4-Pad40)") (class "Default")
      (node (ref "J4") (pin "40") (pinfunction "40_40") (pintype "passive+no_connect"))
    )
    (net (code "127") (name "unconnected-(J4-Pad42)") (class "Default")
      (node (ref "J4") (pin "42") (pinfunction "42_42") (pintype "passive+no_connect"))
    )
    (net (code "128") (name "unconnected-(J4-Pad43)") (class "Default")
      (node (ref "J4") (pin "43") (pinfunction "43_43") (pintype "passive+no_connect"))
    )
    (net (code "129") (name "unconnected-(J4-Pad44)") (class "Default")
      (node (ref "J4") (pin "44") (pinfunction "44_44") (pintype "passive+no_connect"))
    )
    (net (code "130") (name "unconnected-(J4-Pad45)") (class "Default")
      (node (ref "J4") (pin "45") (pinfunction "45_45") (pintype "passive+no_connect"))
    )
    (net (code "131") (name "unconnected-(J4-Pad46)") (class "Default")
      (node (ref "J4") (pin "46") (pinfunction "46_46") (pintype "passive+no_connect"))
    )
    (net (code "132") (name "unconnected-(J4-Pad48)") (class "Default")
      (node (ref "J4") (pin "48") (pinfunction "48_48") (pintype "passive+no_connect"))
    )
    (net (code "133") (name "unconnected-(J4-Pad49)") (class "Default")
      (node (ref "J4") (pin "49") (pinfunction "49_49") (pintype "passive+no_connect"))
    )
    (net (code "134") (name "unconnected-(J5-Pad2)") (class "Default")
      (node (ref "J5") (pin "2") (pinfunction "2_2") (pintype "passive+no_connect"))
    )
    (net (code "135") (name "unconnected-(J5-Pad3)") (class "Default")
      (node (ref "J5") (pin "3") (pinfunction "3_3") (pintype "passive+no_connect"))
    )
    (net (code "136") (name "unconnected-(J5-Pad5)") (class "Default")
      (node (ref "J5") (pin "5") (pinfunction "5_5") (pintype "passive+no_connect"))
    )
    (net (code "137") (name "unconnected-(J5-Pad6)") (class "Default")
      (node (ref "J5") (pin "6") (pinfunction "6_6") (pintype "passive+no_connect"))
    )
    (net (code "138") (name "unconnected-(J5-Pad7)") (class "Default")
      (node (ref "J5") (pin "7") (pinfunction "7_7") (pintype "passive+no_connect"))
    )
    (net (code "139") (name "unconnected-(J5-Pad8)") (class "Default")
      (node (ref "J5") (pin "8") (pinfunction "8_8") (pintype "passive+no_connect"))
    )
    (net (code "140") (name "unconnected-(J5-Pad9)") (class "Default")
      (node (ref "J5") (pin "9") (pinfunction "9_9") (pintype "passive+no_connect"))
    )
    (net (code "141") (name "unconnected-(J5-Pad11)") (class "Default")
      (node (ref "J5") (pin "11") (pinfunction "11_11") (pintype "passive+no_connect"))
    )
    (net (code "142") (name "unconnected-(J5-Pad12)") (class "Default")
      (node (ref "J5") (pin "12") (pinfunction "12_12") (pintype "passive+no_connect"))
    )
    (net (code "143") (name "unconnected-(J5-Pad13)") (class "Default")
      (node (ref "J5") (pin "13") (pinfunction "13_13") (pintype "passive+no_connect"))
    )
    (net (code "144") (name "unconnected-(J5-Pad14)") (class "Default")
      (node (ref "J5") (pin "14") (pinfunction "14_14") (pintype "passive+no_connect"))
    )
    (net (code "145") (name "unconnected-(J5-Pad15)") (class "Default")
      (node (ref "J5") (pin "15") (pinfunction "15_15") (pintype "passive+no_connect"))
    )
    (net (code "146") (name "unconnected-(J5-Pad17)") (class "Default")
      (node (ref "J5") (pin "17") (pinfunction "17_17") (pintype "passive+no_connect"))
    )
    (net (code "147") (name "unconnected-(J5-Pad18)") (class "Default")
      (node (ref "J5") (pin "18") (pinfunction "18_18") (pintype "passive+no_connect"))
    )
    (net (code "148") (name "unconnected-(J5-Pad19)") (class "Default")
      (node (ref "J5") (pin "19") (pinfunction "19_19") (pintype "passive+no_connect"))
    )
    (net (code "149") (name "unconnected-(J5-Pad20)") (class "Default")
      (node (ref "J5") (pin "20") (pinfunction "20_20") (pintype "passive+no_connect"))
    )
    (net (code "150") (name "unconnected-(J5-Pad21)") (class "Default")
      (node (ref "J5") (pin "21") (pinfunction "21_21") (pintype "passive+no_connect"))
    )
    (net (code "151") (name "unconnected-(J5-Pad23)") (class "Default")
      (node (ref "J5") (pin "23") (pinfunction "23_23") (pintype "passive+no_connect"))
    )
    (net (code "152") (name "unconnected-(J5-Pad24)") (class "Default")
      (node (ref "J5") (pin "24") (pinfunction "24_24") (pintype "passive+no_connect"))
    )
    (net (code "153") (name "unconnected-(J5-Pad25)") (class "Default")
      (node (ref "J5") (pin "25") (pinfunction "25_25") (pintype "passive+no_connect"))
    )
    (net (code "154") (name "unconnected-(J5-Pad26)") (class "Default")
      (node (ref "J5") (pin "26") (pinfunction "26_26") (pintype "passive+no_connect"))
    )
    (net (code "155") (name "unconnected-(J5-Pad27)") (class "Default")
      (node (ref "J5") (pin "27") (pinfunction "27_27") (pintype "passive+no_connect"))
    )
    (net (code "156") (name "unconnected-(J5-Pad28)") (class "Default")
      (node (ref "J5") (pin "28") (pinfunction "28_28") (pintype "passive+no_connect"))
    )
    (net (code "157") (name "unconnected-(J5-Pad30)") (class "Default")
      (node (ref "J5") (pin "30") (pinfunction "30_30") (pintype "passive+no_connect"))
    )
    (net (code "158") (name "unconnected-(J5-Pad31)") (class "Default")
      (node (ref "J5") (pin "31") (pinfunction "31_31") (pintype "passive+no_connect"))
    )
    (net (code "159") (name "unconnected-(J5-Pad32)") (class "Default")
      (node (ref "J5") (pin "32") (pinfunction "32_32") (pintype "passive+no_connect"))
    )
    (net (code "160") (name "unconnected-(J5-Pad33)") (class "Default")
      (node (ref "J5") (pin "33") (pinfunction "33_33") (pintype "passive+no_connect"))
    )
    (net (code "161") (name "unconnected-(J5-Pad34)") (class "Default")
      (node (ref "J5") (pin "34") (pinfunction "34_34") (pintype "passive+no_connect"))
    )
    (net (code "162") (name "unconnected-(J5-Pad36)") (class "Default")
      (node (ref "J5") (pin "36") (pinfunction "36_36") (pintype "passive+no_connect"))
    )
    (net (code "163") (name "unconnected-(J5-Pad37)") (class "Default")
      (node (ref "J5") (pin "37") (pinfunction "37_37") (pintype "passive+no_connect"))
    )
    (net (code "164") (name "unconnected-(J5-Pad38)") (class "Default")
      (node (ref "J5") (pin "38") (pinfunction "38_38") (pintype "passive+no_connect"))
    )
    (net (code "165") (name "unconnected-(J5-Pad39)") (class "Default")
      (node (ref "J5") (pin "39") (pinfunction "39_39") (pintype "passive+no_connect"))
    )
    (net (code "166") (name "unconnected-(J5-Pad40)") (class "Default")
      (node (ref "J5") (pin "40") (pinfunction "40_40") (pintype "passive+no_connect"))
    )
    (net (code "167") (name "unconnected-(J5-Pad42)") (class "Default")
      (node (ref "J5") (pin "42") (pinfunction "42_42") (pintype "passive+no_connect"))
    )
    (net (code "168") (name "unconnected-(J5-Pad43)") (class "Default")
      (node (ref "J5") (pin "43") (pinfunction "43_43") (pintype "passive+no_connect"))
    )
    (net (code "169") (name "unconnected-(J5-Pad44)") (class "Default")
      (node (ref "J5") (pin "44") (pinfunction "44_44") (pintype "passive+no_connect"))
    )
    (net (code "170") (name "unconnected-(J5-Pad45)") (class "Default")
      (node (ref "J5") (pin "45") (pinfunction "45_45") (pintype "passive+no_connect"))
    )
    (net (code "171") (name "unconnected-(J5-Pad46)") (class "Default")
      (node (ref "J5") (pin "46") (pinfunction "46_46") (pintype "passive+no_connect"))
    )
    (net (code "172") (name "unconnected-(J5-Pad48)") (class "Default")
      (node (ref "J5") (pin "48") (pinfunction "48_48") (pintype "passive+no_connect"))
    )
    (net (code "173") (name "unconnected-(J5-Pad49)") (class "Default")
      (node (ref "J5") (pin "49") (pinfunction "49_49") (pintype "passive+no_connect"))
    )
    (net (code "174") (name "unconnected-(P1-Pad7)") (class "Default")
      (node (ref "P1") (pin "7") (pinfunction "7_7") (pintype "passive+no_connect"))
    )
    (net (code "175") (name "unconnected-(P1-Pad8)") (class "Default")
      (node (ref "P1") (pin "8") (pinfunction "8_8") (pintype "passive+no_connect"))
    )
    (net (code "176") (name "unconnected-(P1-Pad9)") (class "Default")
      (node (ref "P1") (pin "9") (pinfunction "9_9") (pintype "passive+no_connect"))
    )
    (net (code "177") (name "unconnected-(P1-Pad10)") (class "Default")
      (node (ref "P1") (pin "10") (pinfunction "10_10") (pintype "passive+no_connect"))
    )
    (net (code "178") (name "unconnected-(P1-Pad11)") (class "Default")
      (node (ref "P1") (pin "11") (pinfunction "11_11") (pintype "passive+no_connect"))
    )
    (net (code "179") (name "unconnected-(P1-Pad12)") (class "Default")
      (node (ref "P1") (pin "12") (pinfunction "12_12") (pintype "passive+no_connect"))
    )
    (net (code "180") (name "unconnected-(P5-Pad22)") (class "Default")
      (node (ref "P5") (pin "22") (pinfunction "22_22") (pintype "passive+no_connect"))
    )
    (net (code "181") (name "unconnected-(P5-Pad23)") (class "Default")
      (node (ref "P5") (pin "23") (pinfunction "23_23") (pintype "passive+no_connect"))
    )
    (net (code "182") (name "unconnected-(P5-Pad24)") (class "Default")
      (node (ref "P5") (pin "24") (pinfunction "24_24") (pintype "passive+no_connect"))
    )
    (net (code "183") (name "unconnected-(P5-Pad25)") (class "Default")
      (node (ref "P5") (pin "25") (pinfunction "25_25") (pintype "passive+no_connect"))
    )
  )
)
